# repater_i2c.net
KiCad netlist of a schematic drawn in EAGLE
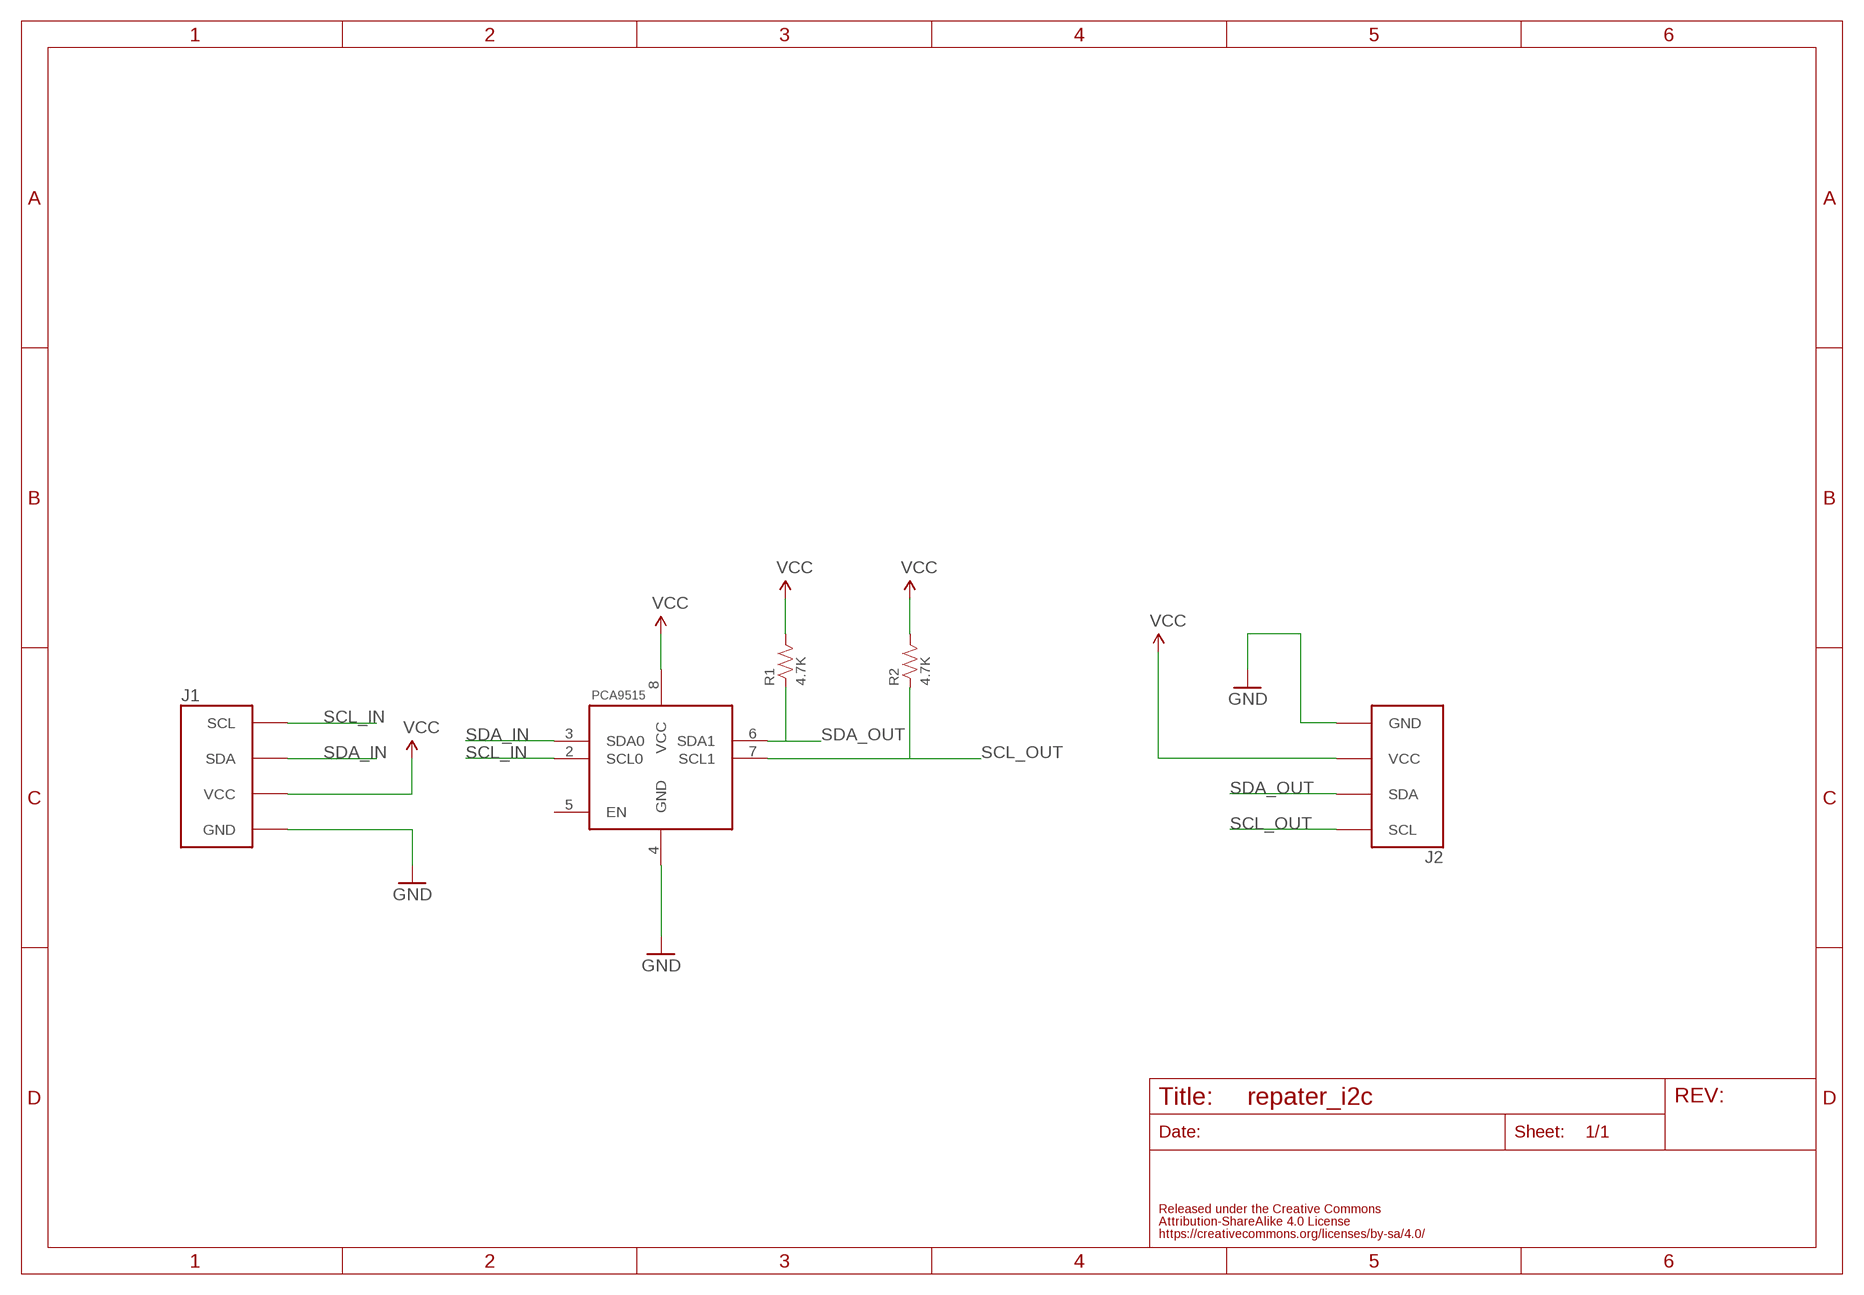
[diagram p0: schematic, sheet 1]

(export (version "E")
  (design (tool "Eeschema 10.0.6"))
  (components
    (comp (ref "J1")
      (value "FABO_BRICK_I2C-S04B-PASK-2_LONG")
      (footprint "eagle-import:FABO_BRICK_I2C_S04B-PASK-2_LONG")
      (libsource (lib "eagle-import") (part "FABO_BRICK_I2C-S04B-PASK-2_LONG"))
    )
    (comp (ref "J2")
      (value "FABO_BRICK_I2C-S04B-PASK-2_LONG")
      (footprint "eagle-import:FABO_BRICK_I2C_S04B-PASK-2_LONG")
      (libsource (lib "eagle-import") (part "FABO_BRICK_I2C-S04B-PASK-2_LONG"))
    )
    (comp (ref "PCA9515")
      (value "PCA9515")
      (footprint "eagle-import:SO8")
      (libsource (lib "eagle-import") (part "PCA9515"))
    )
    (comp (ref "R1")
      (value "4.7K")
      (footprint "eagle-import:0603")
      (libsource (lib "eagle-import") (part "RESISTOR-0603"))
    )
    (comp (ref "R2")
      (value "4.7K")
      (footprint "eagle-import:0603")
      (libsource (lib "eagle-import") (part "RESISTOR-0603"))
    )
  )
  (nets
    (net (code "1") (name "/SCL_IN") (class "Default")
      (node (ref "J1") (pin "SCL") (pinfunction "SCL_SCL") (pintype "bidirectional"))
      (node (ref "PCA9515") (pin "2") (pinfunction "SCL0_2") (pintype "bidirectional"))
    )
    (net (code "2") (name "/SCL_OUT") (class "Default")
      (node (ref "J2") (pin "SCL") (pinfunction "SCL_SCL") (pintype "bidirectional"))
      (node (ref "PCA9515") (pin "7") (pinfunction "SCL1_7") (pintype "bidirectional"))
      (node (ref "R2") (pin "1") (pinfunction "1_1") (pintype "bidirectional"))
    )
    (net (code "3") (name "/SDA_IN") (class "Default")
      (node (ref "J1") (pin "SDA") (pinfunction "SDA_SDA") (pintype "bidirectional"))
      (node (ref "PCA9515") (pin "3") (pinfunction "SDA0_3") (pintype "bidirectional"))
    )
    (net (code "4") (name "/SDA_OUT") (class "Default")
      (node (ref "J2") (pin "SDA") (pinfunction "SDA_SDA") (pintype "bidirectional"))
      (node (ref "PCA9515") (pin "6") (pinfunction "SDA1_6") (pintype "bidirectional"))
      (node (ref "R1") (pin "1") (pinfunction "1_1") (pintype "bidirectional"))
    )
    (net (code "5") (name "GND") (class "Default")
      (node (ref "J1") (pin "GND") (pinfunction "GND_GND") (pintype "bidirectional"))
      (node (ref "J2") (pin "GND") (pinfunction "GND_GND") (pintype "bidirectional"))
      (node (ref "PCA9515") (pin "4") (pinfunction "GND_4") (pintype "bidirectional"))
    )
    (net (code "6") (name "VCC") (class "Default")
      (node (ref "J1") (pin "VCC") (pinfunction "VCC_VCC") (pintype "bidirectional"))
      (node (ref "J2") (pin "VCC") (pinfunction "VCC_VCC") (pintype "bidirectional"))
      (node (ref "PCA9515") (pin "8") (pinfunction "VCC_8") (pintype "bidirectional"))
      (node (ref "R1") (pin "2") (pinfunction "2_2") (pintype "bidirectional"))
      (node (ref "R2") (pin "2") (pinfunction "2_2") (pintype "bidirectional"))
    )
    (net (code "7") (name "unconnected-(PCA9515-EN-Pad5)") (class "Default")
      (node (ref "PCA9515") (pin "5") (pinfunction "EN_5") (pintype "bidirectional"))
    )
  )
)
